# Mixer.net
KiCad netlist of a schematic drawn in EAGLE
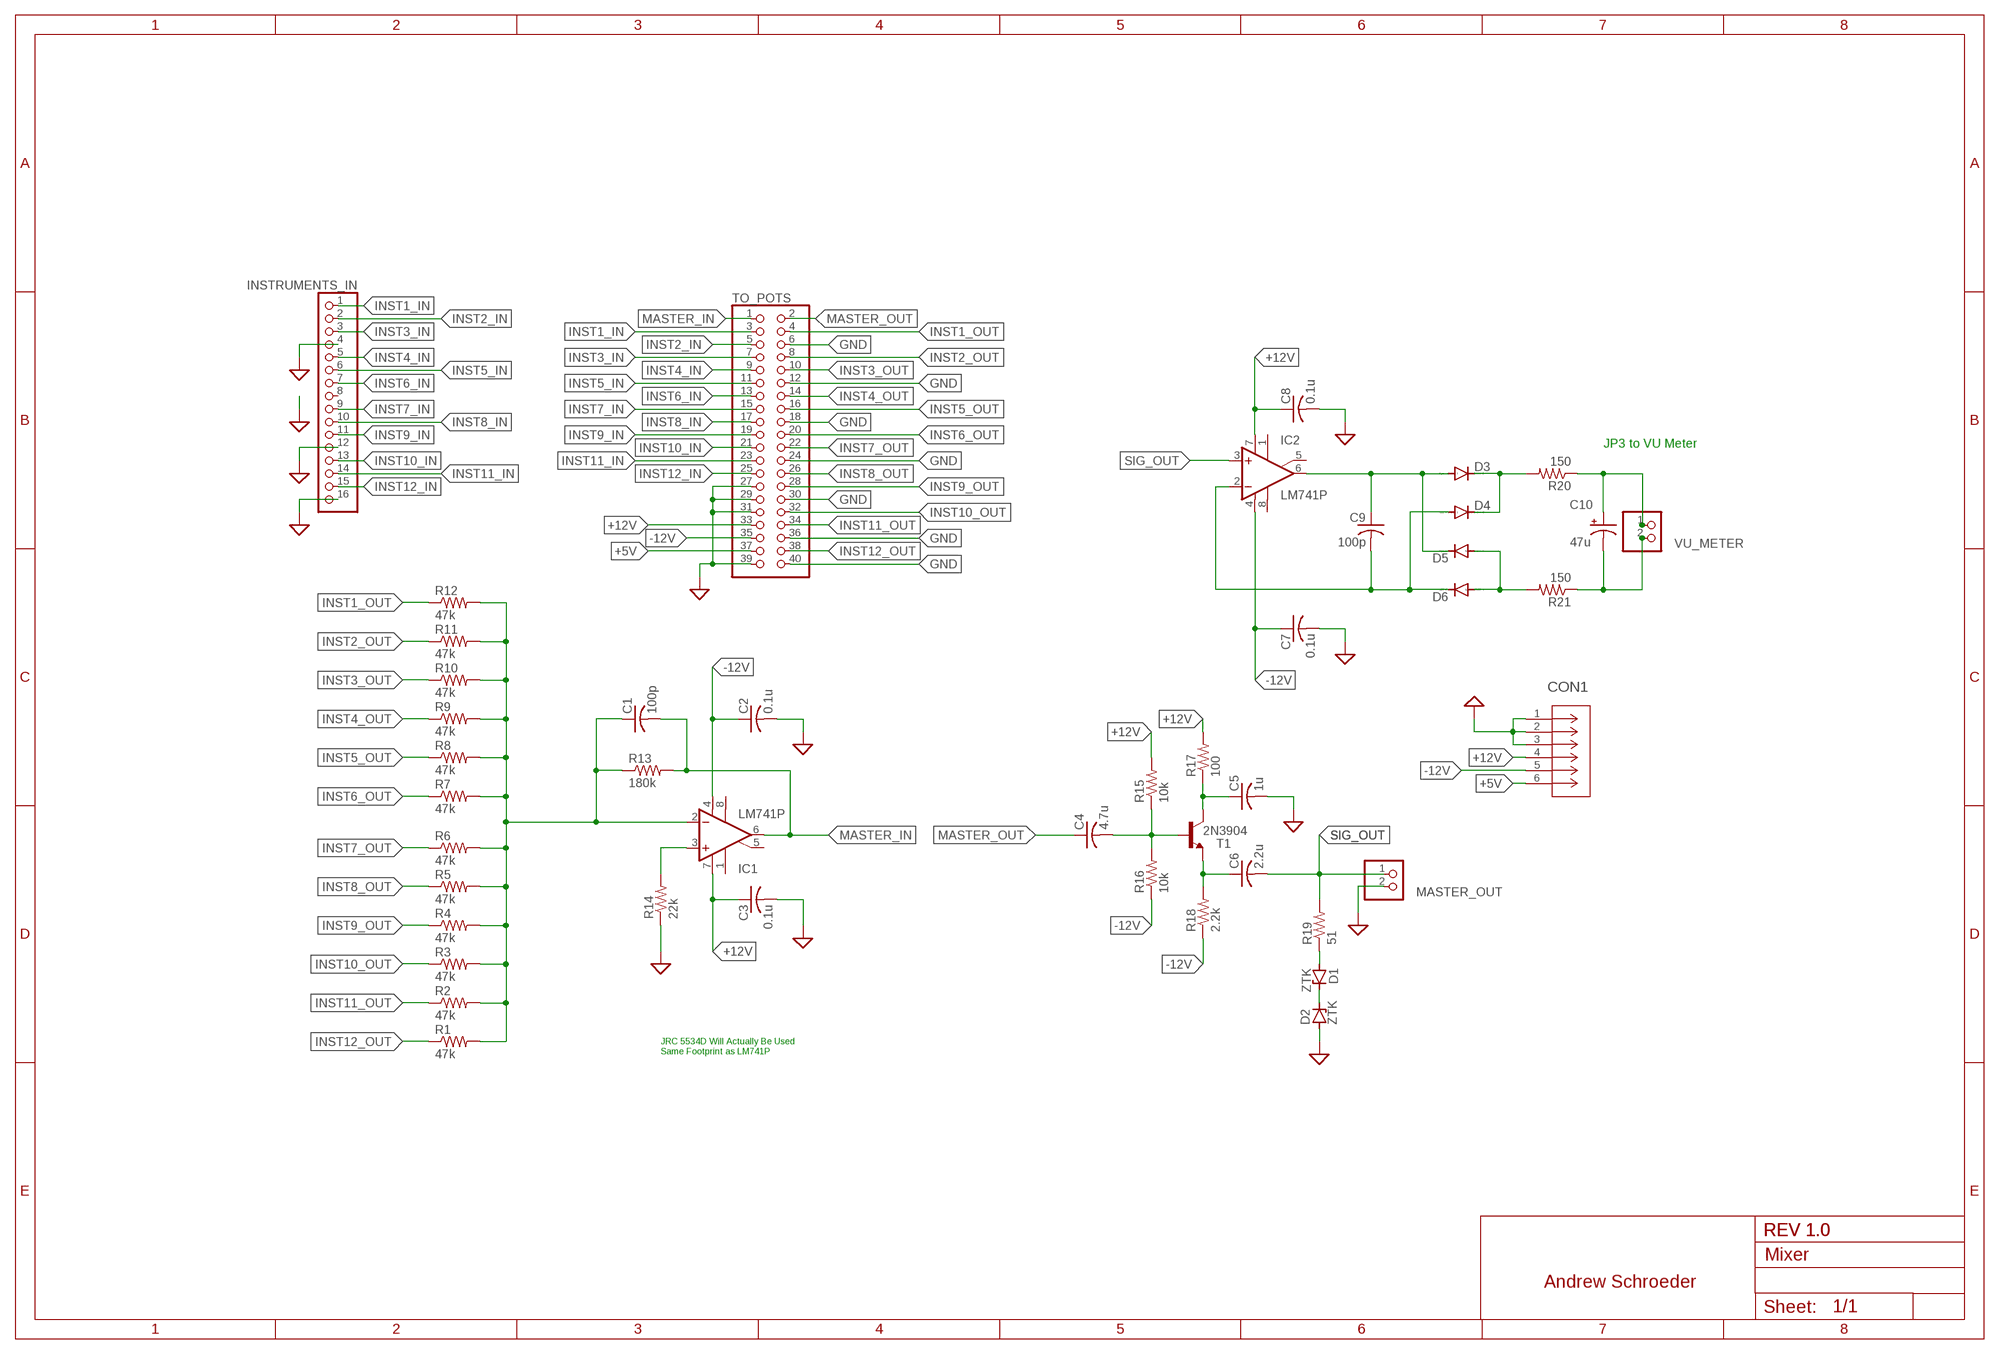
[diagram p0: schematic, sheet 1]

(export (version "E")
  (design (tool "Eeschema 10.0.6"))
  (components
    (comp (ref "C1")
      (value "100p")
      (footprint "eagle-import:C025-025X050")
      (libsource (lib "eagle-import") (part "C-US025-025X050"))
    )
    (comp (ref "C2")
      (value "0.1u")
      (footprint "eagle-import:C025-025X050")
      (libsource (lib "eagle-import") (part "C-US025-025X050"))
    )
    (comp (ref "C3")
      (value "0.1u")
      (footprint "eagle-import:C025-025X050")
      (libsource (lib "eagle-import") (part "C-US025-025X050"))
    )
    (comp (ref "C4")
      (value "4.7u")
      (footprint "eagle-import:C025-025X050")
      (libsource (lib "eagle-import") (part "C-US025-025X050"))
    )
    (comp (ref "C5")
      (value "1u")
      (footprint "eagle-import:C025-025X050")
      (libsource (lib "eagle-import") (part "C-US025-025X050"))
    )
    (comp (ref "C6")
      (value "2.2u")
      (footprint "eagle-import:C025-025X050")
      (libsource (lib "eagle-import") (part "C-US025-025X050"))
    )
    (comp (ref "C7")
      (value "0.1u")
      (footprint "eagle-import:C025-025X050")
      (libsource (lib "eagle-import") (part "C-US025-025X050"))
    )
    (comp (ref "C8")
      (value "0.1u")
      (footprint "eagle-import:C025-025X050")
      (libsource (lib "eagle-import") (part "C-US025-025X050"))
    )
    (comp (ref "C9")
      (value "100p")
      (footprint "eagle-import:C025-025X050")
      (libsource (lib "eagle-import") (part "C-US025-025X050"))
    )
    (comp (ref "C10")
      (value "47u")
      (footprint "eagle-import:E2-5")
      (libsource (lib "eagle-import") (part "CPOL-USE2-5"))
    )
    (comp (ref "CON1")
      (value "1-770875-01-770875-0_VERTICAL")
      (footprint "eagle-import:1-770875-0")
      (libsource (lib "eagle-import") (part "1-770875-01-770875-0_VERTICAL"))
    )
    (comp (ref "D1")
      (value "ZTK")
      (footprint "eagle-import:DO35Z10")
      (libsource (lib "eagle-import") (part "ZTK"))
    )
    (comp (ref "D2")
      (value "ZTK")
      (footprint "eagle-import:DO35Z10")
      (libsource (lib "eagle-import") (part "ZTK"))
    )
    (comp (ref "D3")
      (value "1N4148DO35-7")
      (footprint "eagle-import:DO35-7")
      (libsource (lib "eagle-import") (part "1N4148DO35-7"))
    )
    (comp (ref "D4")
      (value "1N4148DO35-7")
      (footprint "eagle-import:DO35-7")
      (libsource (lib "eagle-import") (part "1N4148DO35-7"))
    )
    (comp (ref "D5")
      (value "1N4148DO35-7")
      (footprint "eagle-import:DO35-7")
      (libsource (lib "eagle-import") (part "1N4148DO35-7"))
    )
    (comp (ref "D6")
      (value "1N4148DO35-7")
      (footprint "eagle-import:DO35-7")
      (libsource (lib "eagle-import") (part "1N4148DO35-7"))
    )
    (comp (ref "IC1")
      (value "LM741P")
      (footprint "eagle-import:DIL08")
      (libsource (lib "eagle-import") (part "741PLM"))
    )
    (comp (ref "IC2")
      (value "LM741P")
      (footprint "eagle-import:DIL08")
      (libsource (lib "eagle-import") (part "741PLM"))
    )
    (comp (ref "INSTRUMENTS_IN")
      (value "PINHD-1X16")
      (footprint "eagle-import:1X16")
      (libsource (lib "eagle-import") (part "PINHD-1X16"))
    )
    (comp (ref "MASTER_OUT")
      (value "PINHD-1X2")
      (footprint "eagle-import:1X02")
      (libsource (lib "eagle-import") (part "PINHD-1X2"))
    )
    (comp (ref "R1")
      (value "47k")
      (footprint "eagle-import:0207_7")
      (libsource (lib "eagle-import") (part "R-US_0207/7"))
    )
    (comp (ref "R2")
      (value "47k")
      (footprint "eagle-import:0207_7")
      (libsource (lib "eagle-import") (part "R-US_0207/7"))
    )
    (comp (ref "R3")
      (value "47k")
      (footprint "eagle-import:0207_7")
      (libsource (lib "eagle-import") (part "R-US_0207/7"))
    )
    (comp (ref "R4")
      (value "47k")
      (footprint "eagle-import:0207_7")
      (libsource (lib "eagle-import") (part "R-US_0207/7"))
    )
    (comp (ref "R5")
      (value "47k")
      (footprint "eagle-import:0207_7")
      (libsource (lib "eagle-import") (part "R-US_0207/7"))
    )
    (comp (ref "R6")
      (value "47k")
      (footprint "eagle-import:0207_7")
      (libsource (lib "eagle-import") (part "R-US_0207/7"))
    )
    (comp (ref "R7")
      (value "47k")
      (footprint "eagle-import:0207_7")
      (libsource (lib "eagle-import") (part "R-US_0207/7"))
    )
    (comp (ref "R8")
      (value "47k")
      (footprint "eagle-import:0207_7")
      (libsource (lib "eagle-import") (part "R-US_0207/7"))
    )
    (comp (ref "R9")
      (value "47k")
      (footprint "eagle-import:0207_7")
      (libsource (lib "eagle-import") (part "R-US_0207/7"))
    )
    (comp (ref "R10")
      (value "47k")
      (footprint "eagle-import:0207_7")
      (libsource (lib "eagle-import") (part "R-US_0207/7"))
    )
    (comp (ref "R11")
      (value "47k")
      (footprint "eagle-import:0207_7")
      (libsource (lib "eagle-import") (part "R-US_0207/7"))
    )
    (comp (ref "R12")
      (value "47k")
      (footprint "eagle-import:0207_7")
      (libsource (lib "eagle-import") (part "R-US_0207/7"))
    )
    (comp (ref "R13")
      (value "180k")
      (footprint "eagle-import:0207_7")
      (libsource (lib "eagle-import") (part "R-US_0207/7"))
    )
    (comp (ref "R14")
      (value "22k")
      (footprint "eagle-import:0207_7")
      (libsource (lib "eagle-import") (part "R-US_0207/7"))
    )
    (comp (ref "R15")
      (value "10k")
      (footprint "eagle-import:0207_7")
      (libsource (lib "eagle-import") (part "R-US_0207/7"))
    )
    (comp (ref "R16")
      (value "10k")
      (footprint "eagle-import:0207_7")
      (libsource (lib "eagle-import") (part "R-US_0207/7"))
    )
    (comp (ref "R17")
      (value "100")
      (footprint "eagle-import:0207_7")
      (libsource (lib "eagle-import") (part "R-US_0207/7"))
    )
    (comp (ref "R18")
      (value "2.2k")
      (footprint "eagle-import:0207_7")
      (libsource (lib "eagle-import") (part "R-US_0207/7"))
    )
    (comp (ref "R19")
      (value "51")
      (footprint "eagle-import:0207_7")
      (libsource (lib "eagle-import") (part "R-US_0207/7"))
    )
    (comp (ref "R20")
      (value "150")
      (footprint "eagle-import:0207_7")
      (libsource (lib "eagle-import") (part "R-US_0207/7"))
    )
    (comp (ref "R21")
      (value "150")
      (footprint "eagle-import:0207_7")
      (libsource (lib "eagle-import") (part "R-US_0207/7"))
    )
    (comp (ref "T1")
      (value "2N3904")
      (footprint "eagle-import:TO92")
      (libsource (lib "eagle-import") (part "2N3904"))
    )
    (comp (ref "TO_POTS")
      (value "PINHD-2X20")
      (footprint "eagle-import:2X20")
      (libsource (lib "eagle-import") (part "PINHD-2X20"))
    )
    (comp (ref "VU_METER")
      (value "PINHD-1X2")
      (footprint "eagle-import:1X02")
      (libsource (lib "eagle-import") (part "PINHD-1X2"))
    )
  )
  (nets
    (net (code "1") (name "+5V") (class "Default")
      (node (ref "CON1") (pin "6") (pinfunction "6_6") (pintype "passive"))
      (node (ref "TO_POTS") (pin "37") (pinfunction "37_37") (pintype "passive"))
    )
    (net (code "2") (name "+12V") (class "Default")
      (node (ref "C3") (pin "1") (pinfunction "1_1") (pintype "passive"))
      (node (ref "C8") (pin "1") (pinfunction "1_1") (pintype "passive"))
      (node (ref "CON1") (pin "4") (pinfunction "4_4") (pintype "passive"))
      (node (ref "IC1") (pin "7") (pinfunction "V+_7") (pintype "power_in"))
      (node (ref "IC2") (pin "7") (pinfunction "V+_7") (pintype "power_in"))
      (node (ref "R15") (pin "2") (pinfunction "2_2") (pintype "passive"))
      (node (ref "R17") (pin "2") (pinfunction "2_2") (pintype "passive"))
      (node (ref "TO_POTS") (pin "33") (pinfunction "33_33") (pintype "passive"))
    )
    (net (code "3") (name "-12V") (class "Default")
      (node (ref "C2") (pin "1") (pinfunction "1_1") (pintype "passive"))
      (node (ref "C7") (pin "1") (pinfunction "1_1") (pintype "passive"))
      (node (ref "CON1") (pin "5") (pinfunction "5_5") (pintype "passive"))
      (node (ref "IC1") (pin "4") (pinfunction "V-_4") (pintype "power_in"))
      (node (ref "IC2") (pin "4") (pinfunction "V-_4") (pintype "power_in"))
      (node (ref "R16") (pin "1") (pinfunction "1_1") (pintype "passive"))
      (node (ref "R18") (pin "1") (pinfunction "1_1") (pintype "passive"))
      (node (ref "TO_POTS") (pin "35") (pinfunction "35_35") (pintype "passive"))
    )
    (net (code "4") (name "GND") (class "Default")
      (node (ref "C2") (pin "2") (pinfunction "2_2") (pintype "passive"))
      (node (ref "C3") (pin "2") (pinfunction "2_2") (pintype "passive"))
      (node (ref "C5") (pin "2") (pinfunction "2_2") (pintype "passive"))
      (node (ref "C7") (pin "2") (pinfunction "2_2") (pintype "passive"))
      (node (ref "C8") (pin "2") (pinfunction "2_2") (pintype "passive"))
      (node (ref "CON1") (pin "1") (pinfunction "1_1") (pintype "passive"))
      (node (ref "CON1") (pin "2") (pinfunction "2_2") (pintype "passive"))
      (node (ref "CON1") (pin "3") (pinfunction "3_3") (pintype "passive"))
      (node (ref "D2") (pin "A") (pinfunction "A_A") (pintype "passive"))
      (node (ref "INSTRUMENTS_IN") (pin "12") (pinfunction "12_12") (pintype "passive"))
      (node (ref "INSTRUMENTS_IN") (pin "16") (pinfunction "16_16") (pintype "passive"))
      (node (ref "INSTRUMENTS_IN") (pin "4") (pinfunction "4_4") (pintype "passive"))
      (node (ref "MASTER_OUT") (pin "2") (pinfunction "2_2") (pintype "passive"))
      (node (ref "R14") (pin "1") (pinfunction "1_1") (pintype "passive"))
      (node (ref "TO_POTS") (pin "12") (pinfunction "12_12") (pintype "passive"))
      (node (ref "TO_POTS") (pin "18") (pinfunction "18_18") (pintype "passive"))
      (node (ref "TO_POTS") (pin "24") (pinfunction "24_24") (pintype "passive"))
      (node (ref "TO_POTS") (pin "27") (pinfunction "27_27") (pintype "passive"))
      (node (ref "TO_POTS") (pin "29") (pinfunction "29_29") (pintype "passive"))
      (node (ref "TO_POTS") (pin "30") (pinfunction "30_30") (pintype "passive"))
      (node (ref "TO_POTS") (pin "31") (pinfunction "31_31") (pintype "passive"))
      (node (ref "TO_POTS") (pin "36") (pinfunction "36_36") (pintype "passive"))
      (node (ref "TO_POTS") (pin "39") (pinfunction "39_39") (pintype "passive"))
      (node (ref "TO_POTS") (pin "40") (pinfunction "40_40") (pintype "passive"))
      (node (ref "TO_POTS") (pin "6") (pinfunction "6_6") (pintype "passive"))
    )
    (net (code "5") (name "INST1_IN") (class "Default")
      (node (ref "INSTRUMENTS_IN") (pin "1") (pinfunction "1_1") (pintype "passive"))
      (node (ref "TO_POTS") (pin "3") (pinfunction "3_3") (pintype "passive"))
    )
    (net (code "6") (name "INST1_OUT") (class "Default")
      (node (ref "R12") (pin "1") (pinfunction "1_1") (pintype "passive"))
      (node (ref "TO_POTS") (pin "4") (pinfunction "4_4") (pintype "passive"))
    )
    (net (code "7") (name "INST2_IN") (class "Default")
      (node (ref "INSTRUMENTS_IN") (pin "2") (pinfunction "2_2") (pintype "passive"))
      (node (ref "TO_POTS") (pin "5") (pinfunction "5_5") (pintype "passive"))
    )
    (net (code "8") (name "INST2_OUT") (class "Default")
      (node (ref "R11") (pin "1") (pinfunction "1_1") (pintype "passive"))
      (node (ref "TO_POTS") (pin "8") (pinfunction "8_8") (pintype "passive"))
    )
    (net (code "9") (name "INST3_IN") (class "Default")
      (node (ref "INSTRUMENTS_IN") (pin "3") (pinfunction "3_3") (pintype "passive"))
      (node (ref "TO_POTS") (pin "7") (pinfunction "7_7") (pintype "passive"))
    )
    (net (code "10") (name "INST3_OUT") (class "Default")
      (node (ref "R10") (pin "1") (pinfunction "1_1") (pintype "passive"))
      (node (ref "TO_POTS") (pin "10") (pinfunction "10_10") (pintype "passive"))
    )
    (net (code "11") (name "INST4_IN") (class "Default")
      (node (ref "INSTRUMENTS_IN") (pin "5") (pinfunction "5_5") (pintype "passive"))
      (node (ref "TO_POTS") (pin "9") (pinfunction "9_9") (pintype "passive"))
    )
    (net (code "12") (name "INST4_OUT") (class "Default")
      (node (ref "R9") (pin "1") (pinfunction "1_1") (pintype "passive"))
      (node (ref "TO_POTS") (pin "14") (pinfunction "14_14") (pintype "passive"))
    )
    (net (code "13") (name "INST5_IN") (class "Default")
      (node (ref "INSTRUMENTS_IN") (pin "6") (pinfunction "6_6") (pintype "passive"))
      (node (ref "TO_POTS") (pin "11") (pinfunction "11_11") (pintype "passive"))
    )
    (net (code "14") (name "INST5_OUT") (class "Default")
      (node (ref "R8") (pin "1") (pinfunction "1_1") (pintype "passive"))
      (node (ref "TO_POTS") (pin "16") (pinfunction "16_16") (pintype "passive"))
    )
    (net (code "15") (name "INST6_IN") (class "Default")
      (node (ref "INSTRUMENTS_IN") (pin "7") (pinfunction "7_7") (pintype "passive"))
      (node (ref "TO_POTS") (pin "13") (pinfunction "13_13") (pintype "passive"))
    )
    (net (code "16") (name "INST6_OUT") (class "Default")
      (node (ref "R7") (pin "1") (pinfunction "1_1") (pintype "passive"))
      (node (ref "TO_POTS") (pin "20") (pinfunction "20_20") (pintype "passive"))
    )
    (net (code "17") (name "INST7_IN") (class "Default")
      (node (ref "INSTRUMENTS_IN") (pin "9") (pinfunction "9_9") (pintype "passive"))
      (node (ref "TO_POTS") (pin "15") (pinfunction "15_15") (pintype "passive"))
    )
    (net (code "18") (name "INST7_OUT") (class "Default")
      (node (ref "R6") (pin "1") (pinfunction "1_1") (pintype "passive"))
      (node (ref "TO_POTS") (pin "22") (pinfunction "22_22") (pintype "passive"))
    )
    (net (code "19") (name "INST8_IN") (class "Default")
      (node (ref "INSTRUMENTS_IN") (pin "10") (pinfunction "10_10") (pintype "passive"))
      (node (ref "TO_POTS") (pin "17") (pinfunction "17_17") (pintype "passive"))
    )
    (net (code "20") (name "INST8_OUT") (class "Default")
      (node (ref "R5") (pin "1") (pinfunction "1_1") (pintype "passive"))
      (node (ref "TO_POTS") (pin "26") (pinfunction "26_26") (pintype "passive"))
    )
    (net (code "21") (name "INST9_IN") (class "Default")
      (node (ref "INSTRUMENTS_IN") (pin "11") (pinfunction "11_11") (pintype "passive"))
      (node (ref "TO_POTS") (pin "19") (pinfunction "19_19") (pintype "passive"))
    )
    (net (code "22") (name "INST9_OUT") (class "Default")
      (node (ref "R4") (pin "1") (pinfunction "1_1") (pintype "passive"))
      (node (ref "TO_POTS") (pin "28") (pinfunction "28_28") (pintype "passive"))
    )
    (net (code "23") (name "INST10_IN") (class "Default")
      (node (ref "INSTRUMENTS_IN") (pin "13") (pinfunction "13_13") (pintype "passive"))
      (node (ref "TO_POTS") (pin "21") (pinfunction "21_21") (pintype "passive"))
    )
    (net (code "24") (name "INST10_OUT") (class "Default")
      (node (ref "R3") (pin "1") (pinfunction "1_1") (pintype "passive"))
      (node (ref "TO_POTS") (pin "32") (pinfunction "32_32") (pintype "passive"))
    )
    (net (code "25") (name "INST11_IN") (class "Default")
      (node (ref "INSTRUMENTS_IN") (pin "14") (pinfunction "14_14") (pintype "passive"))
      (node (ref "TO_POTS") (pin "23") (pinfunction "23_23") (pintype "passive"))
    )
    (net (code "26") (name "INST11_OUT") (class "Default")
      (node (ref "R2") (pin "1") (pinfunction "1_1") (pintype "passive"))
      (node (ref "TO_POTS") (pin "34") (pinfunction "34_34") (pintype "passive"))
    )
    (net (code "27") (name "INST12_IN") (class "Default")
      (node (ref "INSTRUMENTS_IN") (pin "15") (pinfunction "15_15") (pintype "passive"))
      (node (ref "TO_POTS") (pin "25") (pinfunction "25_25") (pintype "passive"))
    )
    (net (code "28") (name "INST12_OUT") (class "Default")
      (node (ref "R1") (pin "1") (pinfunction "1_1") (pintype "passive"))
      (node (ref "TO_POTS") (pin "38") (pinfunction "38_38") (pintype "passive"))
    )
    (net (code "29") (name "MASTER_IN") (class "Default")
      (node (ref "C1") (pin "2") (pinfunction "2_2") (pintype "passive"))
      (node (ref "IC1") (pin "6") (pinfunction "OUT_6") (pintype "output"))
      (node (ref "R13") (pin "2") (pinfunction "2_2") (pintype "passive"))
      (node (ref "TO_POTS") (pin "1") (pinfunction "1_1") (pintype "passive"))
    )
    (net (code "30") (name "MASTER_OUT") (class "Default")
      (node (ref "C4") (pin "1") (pinfunction "1_1") (pintype "passive"))
      (node (ref "TO_POTS") (pin "2") (pinfunction "2_2") (pintype "passive"))
    )
    (net (code "31") (name "Net-(C10-Pad+)") (class "Default")
      (node (ref "C10") (pin "+") (pinfunction "+_+") (pintype "passive"))
      (node (ref "R20") (pin "1") (pinfunction "1_1") (pintype "passive"))
      (node (ref "VU_METER") (pin "1") (pinfunction "1_1") (pintype "passive"))
    )
    (net (code "32") (name "Net-(C10-Pad-)") (class "Default")
      (node (ref "C10") (pin "-") (pinfunction "-_-") (pintype "passive"))
      (node (ref "R21") (pin "1") (pinfunction "1_1") (pintype "passive"))
      (node (ref "VU_METER") (pin "2") (pinfunction "2_2") (pintype "passive"))
    )
    (net (code "33") (name "Net-(D1-PadA)") (class "Default")
      (node (ref "D1") (pin "A") (pinfunction "A_A") (pintype "passive"))
      (node (ref "R19") (pin "1") (pinfunction "1_1") (pintype "passive"))
    )
    (net (code "34") (name "Net-(D1-PadC)") (class "Default")
      (node (ref "D1") (pin "C") (pinfunction "C_C") (pintype "passive"))
      (node (ref "D2") (pin "C") (pinfunction "C_C") (pintype "passive"))
    )
    (net (code "35") (name "Net-(D3-PadC)") (class "Default")
      (node (ref "D3") (pin "C") (pinfunction "C_C") (pintype "passive"))
      (node (ref "D4") (pin "C") (pinfunction "C_C") (pintype "passive"))
      (node (ref "R20") (pin "2") (pinfunction "2_2") (pintype "passive"))
    )
    (net (code "36") (name "Net-(D5-PadA)") (class "Default")
      (node (ref "D5") (pin "A") (pinfunction "A_A") (pintype "passive"))
      (node (ref "D6") (pin "A") (pinfunction "A_A") (pintype "passive"))
      (node (ref "R21") (pin "2") (pinfunction "2_2") (pintype "passive"))
    )
    (net (code "37") (name "Net-(IC1-+IN)") (class "Default")
      (node (ref "IC1") (pin "3") (pinfunction "+IN_3") (pintype "input"))
      (node (ref "R14") (pin "2") (pinfunction "2_2") (pintype "passive"))
    )
    (net (code "38") (name "Net-(IC1--IN)") (class "Default")
      (node (ref "C1") (pin "1") (pinfunction "1_1") (pintype "passive"))
      (node (ref "IC1") (pin "2") (pinfunction "-IN_2") (pintype "input"))
      (node (ref "R1") (pin "2") (pinfunction "2_2") (pintype "passive"))
      (node (ref "R10") (pin "2") (pinfunction "2_2") (pintype "passive"))
      (node (ref "R11") (pin "2") (pinfunction "2_2") (pintype "passive"))
      (node (ref "R12") (pin "2") (pinfunction "2_2") (pintype "passive"))
      (node (ref "R13") (pin "1") (pinfunction "1_1") (pintype "passive"))
      (node (ref "R2") (pin "2") (pinfunction "2_2") (pintype "passive"))
      (node (ref "R3") (pin "2") (pinfunction "2_2") (pintype "passive"))
      (node (ref "R4") (pin "2") (pinfunction "2_2") (pintype "passive"))
      (node (ref "R5") (pin "2") (pinfunction "2_2") (pintype "passive"))
      (node (ref "R6") (pin "2") (pinfunction "2_2") (pintype "passive"))
      (node (ref "R7") (pin "2") (pinfunction "2_2") (pintype "passive"))
      (node (ref "R8") (pin "2") (pinfunction "2_2") (pintype "passive"))
      (node (ref "R9") (pin "2") (pinfunction "2_2") (pintype "passive"))
    )
    (net (code "39") (name "Net-(IC2--IN)") (class "Default")
      (node (ref "C9") (pin "2") (pinfunction "2_2") (pintype "passive"))
      (node (ref "D4") (pin "A") (pinfunction "A_A") (pintype "passive"))
      (node (ref "D6") (pin "C") (pinfunction "C_C") (pintype "passive"))
      (node (ref "IC2") (pin "2") (pinfunction "-IN_2") (pintype "input"))
    )
    (net (code "40") (name "Net-(IC2-OUT)") (class "Default")
      (node (ref "C9") (pin "1") (pinfunction "1_1") (pintype "passive"))
      (node (ref "D3") (pin "A") (pinfunction "A_A") (pintype "passive"))
      (node (ref "D5") (pin "C") (pinfunction "C_C") (pintype "passive"))
      (node (ref "IC2") (pin "6") (pinfunction "OUT_6") (pintype "output"))
    )
    (net (code "41") (name "Net-(T1-B)") (class "Default")
      (node (ref "C4") (pin "2") (pinfunction "2_2") (pintype "passive"))
      (node (ref "R15") (pin "1") (pinfunction "1_1") (pintype "passive"))
      (node (ref "R16") (pin "2") (pinfunction "2_2") (pintype "passive"))
      (node (ref "T1") (pin "2") (pinfunction "B_2") (pintype "passive"))
    )
    (net (code "42") (name "Net-(T1-C)") (class "Default")
      (node (ref "C5") (pin "1") (pinfunction "1_1") (pintype "passive"))
      (node (ref "R17") (pin "1") (pinfunction "1_1") (pintype "passive"))
      (node (ref "T1") (pin "1") (pinfunction "C_1") (pintype "passive"))
    )
    (net (code "43") (name "Net-(T1-E)") (class "Default")
      (node (ref "C6") (pin "1") (pinfunction "1_1") (pintype "passive"))
      (node (ref "R18") (pin "2") (pinfunction "2_2") (pintype "passive"))
      (node (ref "T1") (pin "3") (pinfunction "E_3") (pintype "passive"))
    )
    (net (code "44") (name "SIG_OUT") (class "Default")
      (node (ref "C6") (pin "2") (pinfunction "2_2") (pintype "passive"))
      (node (ref "IC2") (pin "3") (pinfunction "+IN_3") (pintype "input"))
      (node (ref "MASTER_OUT") (pin "1") (pinfunction "1_1") (pintype "passive"))
      (node (ref "R19") (pin "2") (pinfunction "2_2") (pintype "passive"))
    )
    (net (code "45") (name "unconnected-(IC1-ON1-Pad1)") (class "Default")
      (node (ref "IC1") (pin "1") (pinfunction "ON1_1") (pintype "passive"))
    )
    (net (code "46") (name "unconnected-(IC1-ON2-Pad5)") (class "Default")
      (node (ref "IC1") (pin "5") (pinfunction "ON2_5") (pintype "passive"))
    )
    (net (code "47") (name "unconnected-(IC1-OPT-Pad8)") (class "Default")
      (node (ref "IC1") (pin "8") (pinfunction "OPT_8") (pintype "passive"))
    )
    (net (code "48") (name "unconnected-(IC2-ON1-Pad1)") (class "Default")
      (node (ref "IC2") (pin "1") (pinfunction "ON1_1") (pintype "passive"))
    )
    (net (code "49") (name "unconnected-(IC2-ON2-Pad5)") (class "Default")
      (node (ref "IC2") (pin "5") (pinfunction "ON2_5") (pintype "passive"))
    )
    (net (code "50") (name "unconnected-(IC2-OPT-Pad8)") (class "Default")
      (node (ref "IC2") (pin "8") (pinfunction "OPT_8") (pintype "passive"))
    )
    (net (code "51") (name "unconnected-(INSTRUMENTS_IN-Pad8)") (class "Default")
      (node (ref "INSTRUMENTS_IN") (pin "8") (pinfunction "8_8") (pintype "passive"))
    )
  )
)
